# cc2500.net
KiCad netlist of a schematic drawn in Altium Designer
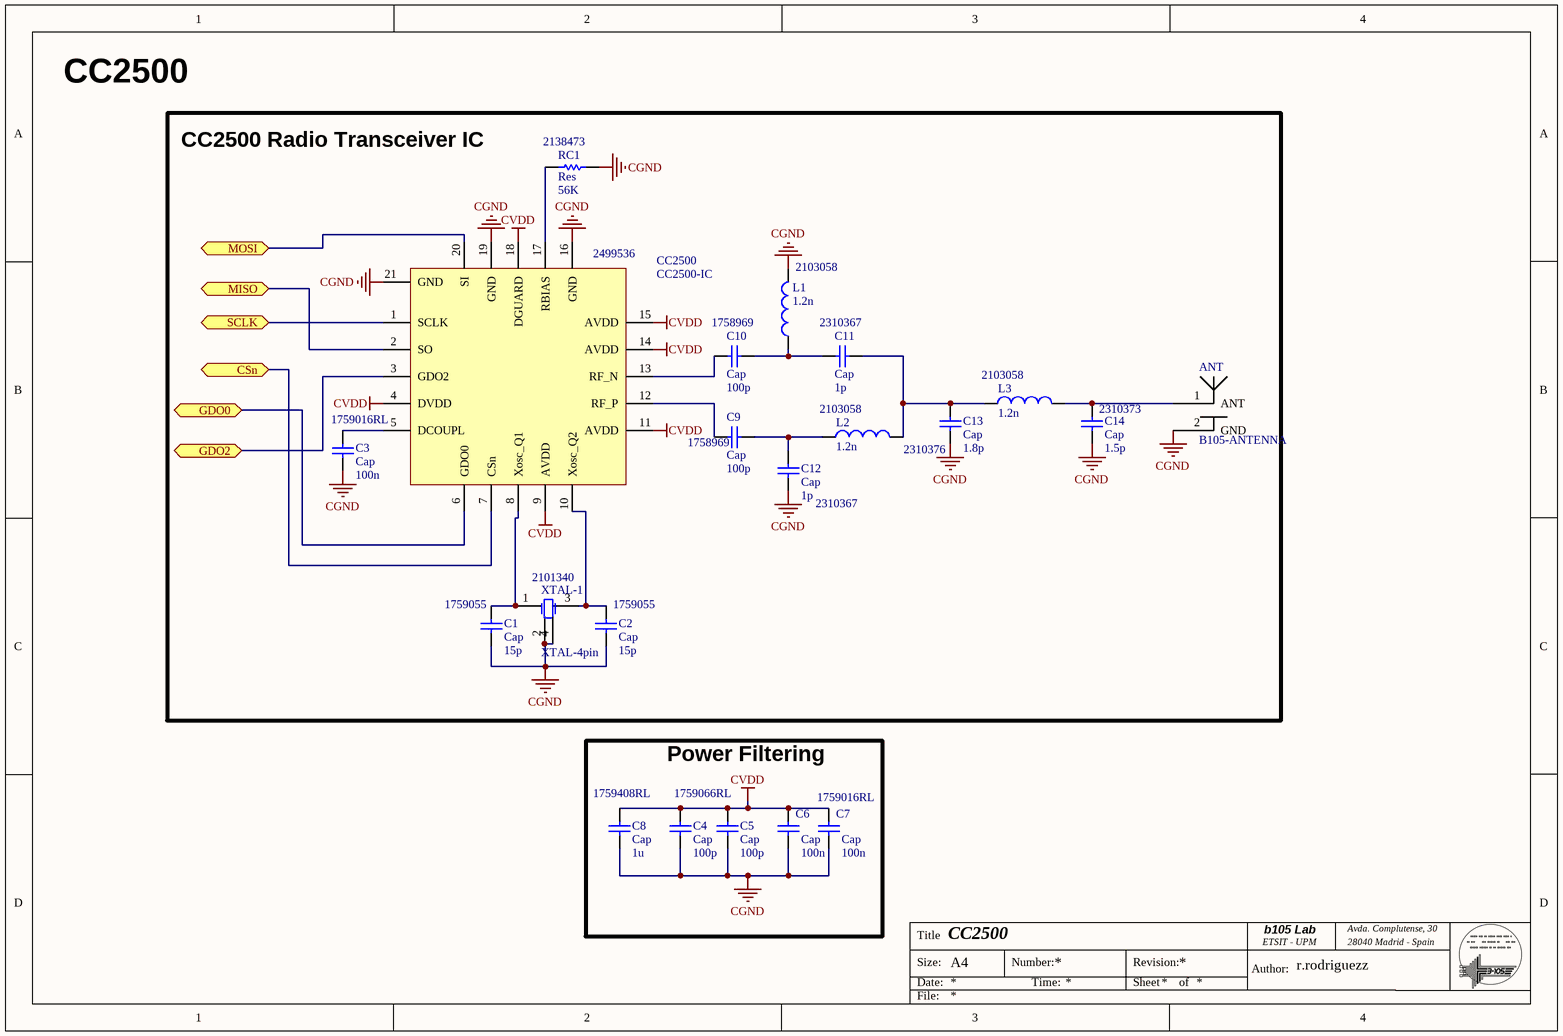
[diagram p0: cc2500.SchDoc]

(export (version "E")
  (design (tool "Eeschema 10.0.6"))
  (components
    (comp (ref "ANT")
      (value "B105-ANTENNA")
      (footprint "B105-Antenna")
      (libsource (lib "B105lib") (part "B105-ANTENNA"))
    )
    (comp (ref "C1")
      (value "Cap")
      (footprint "0603 Cap")
      (fields
        (field (name "ALTIUM_VALUE") "15p")
        (field (name "SUPPLIER PART NUMBER 1") "1759055")
        (field (name "MANUFACTURER") "MULTICOMP")
        (field (name "MANUFACTURER PART NUMBER") "MC0603N150J500CT")
      )
      (libsource (lib "B105lib") (part "Cap"))
    )
    (comp (ref "C2")
      (value "Cap")
      (footprint "0603 Cap")
      (fields
        (field (name "ALTIUM_VALUE") "15p")
        (field (name "SUPPLIER PART NUMBER 1") "1759055")
        (field (name "MANUFACTURER") "MULTICOMP")
        (field (name "MANUFACTURER PART NUMBER") "MC0603N150J500CT")
      )
      (libsource (lib "B105lib") (part "Cap"))
    )
    (comp (ref "C3")
      (value "Cap")
      (footprint "0603 Cap")
      (fields
        (field (name "ALTIUM_VALUE") "100n")
        (field (name "SUPPLIER PART NUMBER 1") "1759016RL")
        (field (name "MANUFACTURER") "MULTICOMP")
        (field (name "MANUFACTURER PART NUMBER") "MC0603B104K160CT")
      )
      (libsource (lib "B105lib") (part "Cap"))
    )
    (comp (ref "C4")
      (value "Cap")
      (footprint "0603 Cap")
      (fields
        (field (name "ALTIUM_VALUE") "100p")
        (field (name "SUPPLIER PART NUMBER 1") "1759066RL")
        (field (name "MANUFACTURER") "MULTICOMP")
        (field (name "MANUFACTURER PART NUMBER") "MC0603N101J500CT")
      )
      (libsource (lib "B105lib") (part "Cap"))
    )
    (comp (ref "C5")
      (value "Cap")
      (footprint "0603 Cap")
      (fields
        (field (name "ALTIUM_VALUE") "100p")
        (field (name "MANUFACTURER") "MULTICOMP")
        (field (name "MANUFACTURER PART NUMBER") "MC0603N101J500CT")
      )
      (libsource (lib "B105lib") (part "Cap"))
    )
    (comp (ref "C6")
      (value "Cap")
      (footprint "0603 Cap")
      (fields
        (field (name "ALTIUM_VALUE") "100n")
        (field (name "MANUFACTURER") "MULTICOMP")
        (field (name "MANUFACTURER PART NUMBER") "MC0603B104K160CT")
      )
      (libsource (lib "B105lib") (part "Cap"))
    )
    (comp (ref "C7")
      (value "Cap")
      (footprint "0603 Cap")
      (fields
        (field (name "ALTIUM_VALUE") "100n")
        (field (name "SUPPLIER PART NUMBER 1") "1759016RL")
        (field (name "MANUFACTURER") "MULTICOMP")
        (field (name "MANUFACTURER PART NUMBER") "MC0603B104K160CT")
      )
      (libsource (lib "B105lib") (part "Cap"))
    )
    (comp (ref "C8")
      (value "Cap")
      (footprint "0603 Cap")
      (fields
        (field (name "ALTIUM_VALUE") "1u")
        (field (name "SUPPLIER PART NUMBER 1") "1759408RL")
        (field (name "MANUFACTURER") "MULTICOMP")
        (field (name "MANUFACTURER PART NUMBER") "MC0603F105Z160CT")
      )
      (libsource (lib "B105lib") (part "Cap"))
    )
    (comp (ref "C9")
      (value "Cap")
      (footprint "0402 CAP")
      (fields
        (field (name "ALTIUM_VALUE") "100p")
        (field (name "SUPPLIER PART NUMBER 1") "1758969")
        (field (name "MANUFACTURER") "MULTICOMP")
        (field (name "MANUFACTURER PART NUMBER") "MC0402N101J500CT")
      )
      (libsource (lib "B105lib") (part "Cap"))
    )
    (comp (ref "C10")
      (value "Cap")
      (footprint "0402 CAP")
      (fields
        (field (name "ALTIUM_VALUE") "100p")
        (field (name "SUPPLIER PART NUMBER 1") "1758969")
        (field (name "MANUFACTURER") "MULTICOMP")
        (field (name "MANUFACTURER PART NUMBER") "MC0402N101J500CT")
      )
      (libsource (lib "B105lib") (part "Cap"))
    )
    (comp (ref "C11")
      (value "Cap")
      (footprint "0402 CAP")
      (fields
        (field (name "ALTIUM_VALUE") "1p")
        (field (name "SUPPLIER PART NUMBER 1") "2310367")
        (field (name "MANUFACTURER") "MULTICOMP")
        (field (name "MANUFACTURER PART NUMBER") "MCRF15N1R0A500CT")
      )
      (libsource (lib "B105lib") (part "Cap"))
    )
    (comp (ref "C12")
      (value "Cap")
      (footprint "0402 CAP")
      (fields
        (field (name "ALTIUM_VALUE") "1p")
        (field (name "SUPPLIER PART NUMBER 1") "2310367")
        (field (name "MANUFACTURER") "MULTICOMP")
        (field (name "MANUFACTURER PART NUMBER") "MCRF15N1R0A500CT")
      )
      (libsource (lib "B105lib") (part "Cap"))
    )
    (comp (ref "C13")
      (value "Cap")
      (footprint "0402 CAP")
      (fields
        (field (name "ALTIUM_VALUE") "1.8p")
        (field (name "SUPPLIER PART NUMBER 1") "2310376")
        (field (name "MANUFACTURER") "MULTICOMP")
        (field (name "MANUFACTURER PART NUMBER") "MCRF15N1R8A500CT")
      )
      (libsource (lib "B105lib") (part "Cap"))
    )
    (comp (ref "C14")
      (value "Cap")
      (footprint "0402 CAP")
      (fields
        (field (name "ALTIUM_VALUE") "1.5p")
        (field (name "SUPPLIER PART NUMBER 1") "2310373")
        (field (name "MANUFACTURER") "MULTICOMP")
        (field (name "MANUFACTURER PART NUMBER") "MCRF15N1R5A500CT")
      )
      (libsource (lib "B105lib") (part "Cap"))
    )
    (comp (ref "CC2500")
      (value "CC2500-IC")
      (footprint "QFN-20")
      (fields
        (field (name "SUPPLIER PART NUMBER 1") "2499536")
        (field (name "MANUFACTURER") "TEXAS INSTRUMENTS")
        (field (name "MANUFACTURER PART NUMBER") "CC2500RGP")
      )
      (libsource (lib "B105lib") (part "CC1101-IC"))
    )
    (comp (ref "L1")
      (value "1.2n")
      (footprint "0402 IND")
      (fields
        (field (name "SUPPLIER PART NUMBER 1") "2103058")
        (field (name "MANUFACTURER") "MULTICOMP")
        (field (name "MANUFACTURER PART NUMBER") "MCFT0BT1N2")
        (field (name "Comment") "L")
      )
      (libsource (lib "B105lib") (part "Ind"))
    )
    (comp (ref "L2")
      (value "1.2n")
      (footprint "0402 IND")
      (fields
        (field (name "SUPPLIER PART NUMBER 1") "2103058")
        (field (name "MANUFACTURER") "MULTICOMP")
        (field (name "MANUFACTURER PART NUMBER") "MCFT0BT1N2")
        (field (name "Comment") "L")
      )
      (libsource (lib "B105lib") (part "Ind"))
    )
    (comp (ref "L3")
      (value "1.2n")
      (footprint "0402 IND")
      (fields
        (field (name "SUPPLIER PART NUMBER 1") "2103058")
        (field (name "MANUFACTURER") "MULTICOMP")
        (field (name "MANUFACTURER PART NUMBER") "MCFT0BT1N2")
        (field (name "Comment") "L")
      )
      (libsource (lib "B105lib") (part "Ind"))
    )
    (comp (ref "RC1")
      (value "Res")
      (footprint "0603 Res")
      (fields
        (field (name "ALTIUM_VALUE") "56K")
        (field (name "SUPPLIER PART NUMBER 1") "2138473")
        (field (name "MANUFACTURER") "VISHAY")
        (field (name "MANUFACTURER PART NUMBER") "CRCW060356K0FKEA.")
      )
      (libsource (lib "B105lib") (part "Res"))
    )
    (comp (ref "XTAL-1")
      (value "XTAL-4pin")
      (footprint "XTAL-4PIN-3.2x2.5mm")
      (fields
        (field (name "SUPPLIER PART NUMBER 1") "2101340")
        (field (name "MANUFACTURER") "ABRACON")
        (field (name "MANUFACTURER PART NUMBER") "ABM8G-26.000MHZ-B4Y-T")
      )
      (libsource (lib "B105lib") (part "XTAL-4pin"))
    )
  )
  (nets
    (net (code "1") (name "/CSn") (class "Default")
      (node (ref "CC2500") (pin "7") (pinfunction "CSn_7") (pintype "passive"))
    )
    (net (code "2") (name "/GDO0") (class "Default")
      (node (ref "CC2500") (pin "6") (pinfunction "GDO0_6") (pintype "passive"))
    )
    (net (code "3") (name "/GDO2") (class "Default")
      (node (ref "CC2500") (pin "3") (pinfunction "GDO2_3") (pintype "passive"))
    )
    (net (code "4") (name "/MISO") (class "Default")
      (node (ref "CC2500") (pin "2") (pinfunction "SO_2") (pintype "passive"))
    )
    (net (code "5") (name "/MOSI") (class "Default")
      (node (ref "CC2500") (pin "20") (pinfunction "SI_20") (pintype "passive"))
    )
    (net (code "6") (name "/SCLK") (class "Default")
      (node (ref "CC2500") (pin "1") (pinfunction "SCLK_1") (pintype "passive"))
    )
    (net (code "7") (name "CGND") (class "Default")
      (node (ref "ANT") (pin "2") (pinfunction "GND_2") (pintype "passive"))
      (node (ref "C1") (pin "1") (pinfunction "1_1") (pintype "passive"))
      (node (ref "C12") (pin "1") (pinfunction "1_1") (pintype "passive"))
      (node (ref "C13") (pin "1") (pinfunction "1_1") (pintype "passive"))
      (node (ref "C14") (pin "1") (pinfunction "1_1") (pintype "passive"))
      (node (ref "C2") (pin "1") (pinfunction "1_1") (pintype "passive"))
      (node (ref "C3") (pin "1") (pinfunction "1_1") (pintype "passive"))
      (node (ref "C4") (pin "1") (pinfunction "1_1") (pintype "passive"))
      (node (ref "C5") (pin "1") (pinfunction "1_1") (pintype "passive"))
      (node (ref "C6") (pin "1") (pinfunction "1_1") (pintype "passive"))
      (node (ref "C7") (pin "1") (pinfunction "1_1") (pintype "passive"))
      (node (ref "C8") (pin "1") (pinfunction "1_1") (pintype "passive"))
      (node (ref "CC2500") (pin "16") (pinfunction "GND_16") (pintype "passive"))
      (node (ref "CC2500") (pin "19") (pinfunction "GND_19") (pintype "passive"))
      (node (ref "CC2500") (pin "21") (pinfunction "GND_21") (pintype "passive"))
      (node (ref "L1") (pin "2") (pinfunction "2_2") (pintype "passive"))
      (node (ref "RC1") (pin "2") (pinfunction "2_2") (pintype "passive"))
      (node (ref "XTAL-1") (pin "2") (pinfunction "GND_2") (pintype "passive"))
      (node (ref "XTAL-1") (pin "4") (pinfunction "GND_4") (pintype "passive"))
    )
    (net (code "8") (name "CVDD") (class "Default")
      (node (ref "C4") (pin "2") (pinfunction "2_2") (pintype "passive"))
      (node (ref "C5") (pin "2") (pinfunction "2_2") (pintype "passive"))
      (node (ref "C6") (pin "2") (pinfunction "2_2") (pintype "passive"))
      (node (ref "C7") (pin "2") (pinfunction "2_2") (pintype "passive"))
      (node (ref "C8") (pin "2") (pinfunction "2_2") (pintype "passive"))
      (node (ref "CC2500") (pin "11") (pinfunction "AVDD_11") (pintype "passive"))
      (node (ref "CC2500") (pin "14") (pinfunction "AVDD_14") (pintype "passive"))
      (node (ref "CC2500") (pin "15") (pinfunction "AVDD_15") (pintype "passive"))
      (node (ref "CC2500") (pin "18") (pinfunction "DGUARD_18") (pintype "passive"))
      (node (ref "CC2500") (pin "4") (pinfunction "DVDD_4") (pintype "passive"))
      (node (ref "CC2500") (pin "9") (pinfunction "AVDD_9") (pintype "passive"))
    )
    (net (code "9") (name "Net-(ANT-ANT)") (class "Default")
      (node (ref "ANT") (pin "1") (pinfunction "ANT_1") (pintype "passive"))
      (node (ref "C14") (pin "2") (pinfunction "2_2") (pintype "passive"))
      (node (ref "L3") (pin "2") (pinfunction "2_2") (pintype "passive"))
    )
    (net (code "10") (name "Net-(C10-Pad2)") (class "Default")
      (node (ref "C10") (pin "2") (pinfunction "2_2") (pintype "passive"))
      (node (ref "C11") (pin "1") (pinfunction "1_1") (pintype "passive"))
      (node (ref "L1") (pin "1") (pinfunction "1_1") (pintype "passive"))
    )
    (net (code "11") (name "Net-(C11-Pad2)") (class "Default")
      (node (ref "C11") (pin "2") (pinfunction "2_2") (pintype "passive"))
      (node (ref "C13") (pin "2") (pinfunction "2_2") (pintype "passive"))
      (node (ref "L2") (pin "2") (pinfunction "2_2") (pintype "passive"))
      (node (ref "L3") (pin "1") (pinfunction "1_1") (pintype "passive"))
    )
    (net (code "12") (name "Net-(C12-Pad2)") (class "Default")
      (node (ref "C12") (pin "2") (pinfunction "2_2") (pintype "passive"))
      (node (ref "C9") (pin "2") (pinfunction "2_2") (pintype "passive"))
      (node (ref "L2") (pin "1") (pinfunction "1_1") (pintype "passive"))
    )
    (net (code "13") (name "Net-(CC2500-DCOUPL)") (class "Default")
      (node (ref "C3") (pin "2") (pinfunction "2_2") (pintype "passive"))
      (node (ref "CC2500") (pin "5") (pinfunction "DCOUPL_5") (pintype "passive"))
    )
    (net (code "14") (name "Net-(CC2500-RBIAS)") (class "Default")
      (node (ref "CC2500") (pin "17") (pinfunction "RBIAS_17") (pintype "passive"))
      (node (ref "RC1") (pin "1") (pinfunction "1_1") (pintype "passive"))
    )
    (net (code "15") (name "Net-(CC2500-RF_N)") (class "Default")
      (node (ref "C10") (pin "1") (pinfunction "1_1") (pintype "passive"))
      (node (ref "CC2500") (pin "13") (pinfunction "RF_N_13") (pintype "passive"))
    )
    (net (code "16") (name "Net-(CC2500-RF_P)") (class "Default")
      (node (ref "C9") (pin "1") (pinfunction "1_1") (pintype "passive"))
      (node (ref "CC2500") (pin "12") (pinfunction "RF_P_12") (pintype "passive"))
    )
    (net (code "17") (name "Net-(CC2500-Xosc_Q1)") (class "Default")
      (node (ref "C1") (pin "2") (pinfunction "2_2") (pintype "passive"))
      (node (ref "CC2500") (pin "8") (pinfunction "Xosc_Q1_8") (pintype "passive"))
      (node (ref "XTAL-1") (pin "1") (pinfunction "OSC1_1") (pintype "passive"))
    )
    (net (code "18") (name "Net-(CC2500-Xosc_Q2)") (class "Default")
      (node (ref "C2") (pin "2") (pinfunction "2_2") (pintype "passive"))
      (node (ref "CC2500") (pin "10") (pinfunction "Xosc_Q2_10") (pintype "passive"))
      (node (ref "XTAL-1") (pin "3") (pinfunction "OSC2_3") (pintype "passive"))
    )
  )
)
